# MiniRS485_RJ45-MySens-v1_7.net
KiCad netlist of a schematic drawn in EAGLE
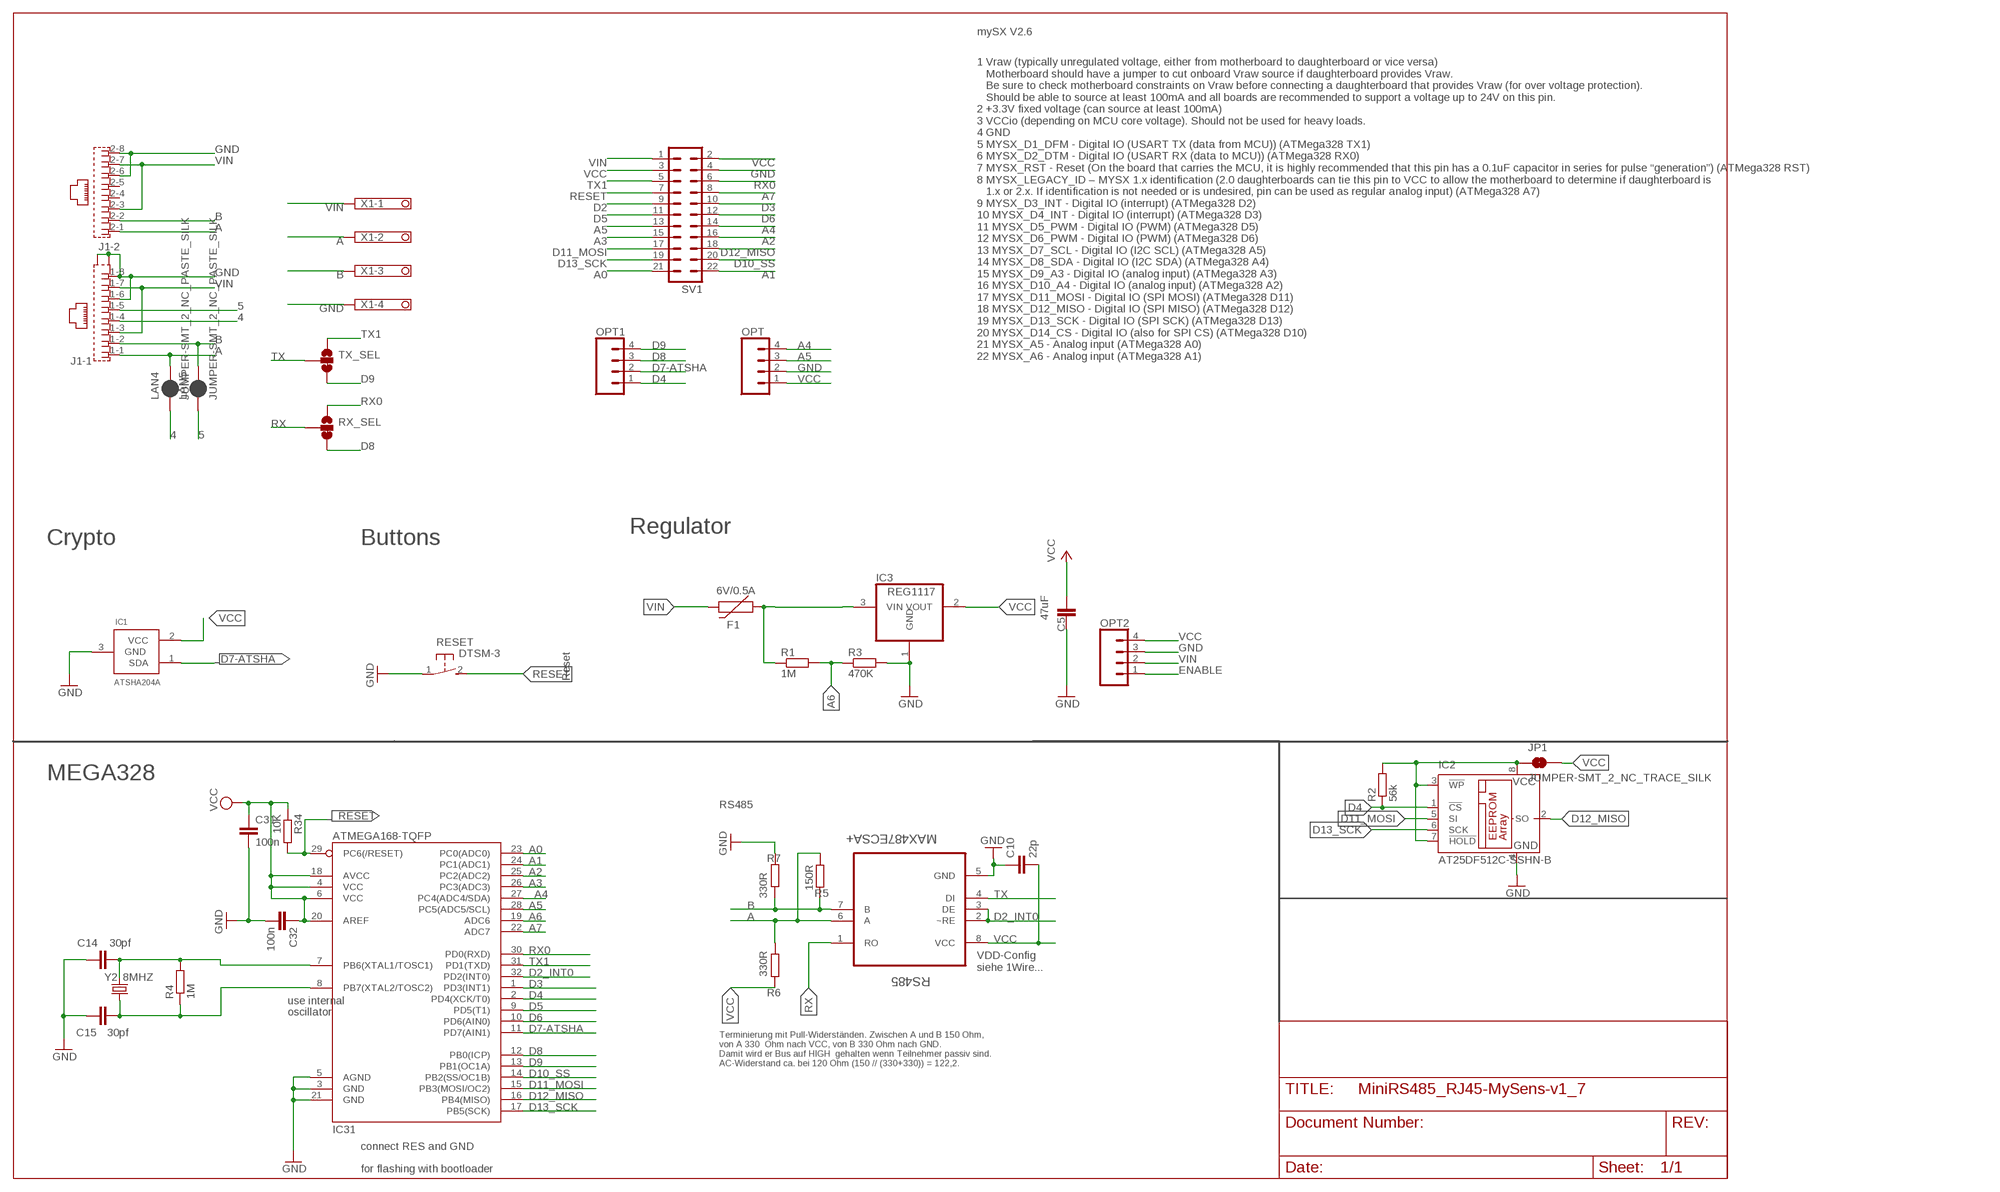
[diagram p0: schematic, sheet 1]

(export (version "E")
  (design (tool "Eeschema 10.0.6"))
  (components
    (comp (ref "C5")
      (value "47uF")
      (footprint "eagle-import:C1210")
      (libsource (lib "eagle-import") (part "C-EUC1210"))
    )
    (comp (ref "C10")
      (value "22p")
      (footprint "eagle-import:C0805")
      (libsource (lib "eagle-import") (part "C-EUC0805"))
    )
    (comp (ref "C14")
      (value "30pf")
      (footprint "eagle-import:C0805")
      (libsource (lib "eagle-import") (part "resistor_C-EUC0805"))
    )
    (comp (ref "C15")
      (value "30pf")
      (footprint "eagle-import:C0805")
      (libsource (lib "eagle-import") (part "resistor_C-EUC0805"))
    )
    (comp (ref "C31")
      (value "100n")
      (footprint "eagle-import:C0805")
      (libsource (lib "eagle-import") (part "C-EUC0805"))
    )
    (comp (ref "C32")
      (value "100n")
      (footprint "eagle-import:C0805")
      (libsource (lib "eagle-import") (part "C-EUC0805"))
    )
    (comp (ref "F1")
      (value "6V/0.5A")
      (footprint "eagle-import:1206")
      (libsource (lib "eagle-import") (part "PPTC_HALF-AMP"))
    )
    (comp (ref "IC1")
      (value "ATSHA204A")
      (footprint "eagle-import:SOT23")
      (libsource (lib "eagle-import") (part "ATSHA204A"))
    )
    (comp (ref "IC2")
      (value "AT25DF512C-SSHN-B")
      (footprint "eagle-import:SO-08")
      (fields (field (name "MF") "MICROCHIP") (field (name "MPN") "25AA080/SN"))
      (libsource (lib "eagle-import") (part "25SNAA080"))
    )
    (comp (ref "IC3")
      (value "REG1117")
      (footprint "eagle-import:SOT223")
      (libsource (lib "eagle-import") (part "REG1117"))
    )
    (comp (ref "IC31")
      (value "ATMEGA168-TQFP")
      (footprint "eagle-import:TQFP32-08")
      (libsource (lib "eagle-import") (part "ATMEGA168-TQFP"))
    )
    (comp (ref "J1")
      (value "RJ45_2X_NARROW_SHILDPINS_NOCASE")
      (footprint "eagle-import:RJ45_2X_NARROW_SHILDPINS_NOCASE")
      (libsource (lib "eagle-import") (part "RJ45_2X_NARROW_SHILDPINS_NOCASE"))
    )
    (comp (ref "JP1")
      (value "JUMPER-SMT_2_NC_TRACE_SILK")
      (footprint "eagle-import:SMT-JUMPER_2_NC_TRACE_SILK")
      (libsource (lib "eagle-import") (part "JUMPER-SMT_2_NC_TRACE_SILK"))
    )
    (comp (ref "LAN4")
      (value "JUMPER-SMT_2_NC_PASTE_SILK")
      (footprint "eagle-import:SMT-JUMPER_2_NC_PASTE_SILK")
      (libsource (lib "eagle-import") (part "JUMPER-SMT_2_NC_PASTE_SILK"))
    )
    (comp (ref "LAN5")
      (value "JUMPER-SMT_2_NC_PASTE_SILK")
      (footprint "eagle-import:SMT-JUMPER_2_NC_PASTE_SILK")
      (libsource (lib "eagle-import") (part "JUMPER-SMT_2_NC_PASTE_SILK"))
    )
    (comp (ref "OPT")
      (value "CONN_04")
      (footprint "eagle-import:1X04")
      (libsource (lib "eagle-import") (part "CONN_04"))
    )
    (comp (ref "OPT1")
      (value "CONN_04")
      (footprint "eagle-import:1X04")
      (libsource (lib "eagle-import") (part "CONN_04"))
    )
    (comp (ref "OPT2")
      (value "CONN_04")
      (footprint "eagle-import:1X04")
      (libsource (lib "eagle-import") (part "CONN_04"))
    )
    (comp (ref "R1")
      (value "1M")
      (footprint "eagle-import:M0805")
      (libsource (lib "eagle-import") (part "R-EU_M0805"))
    )
    (comp (ref "R2")
      (value "56k")
      (footprint "eagle-import:M0805")
      (libsource (lib "eagle-import") (part "resistor_R-EU_M0805"))
    )
    (comp (ref "R3")
      (value "470K")
      (footprint "eagle-import:R0805")
      (libsource (lib "eagle-import") (part "R-EU_R0805"))
    )
    (comp (ref "R4")
      (value "1M")
      (footprint "eagle-import:M0805")
      (libsource (lib "eagle-import") (part "R-EU_M0805"))
    )
    (comp (ref "R5")
      (value "150R")
      (footprint "eagle-import:R0805")
      (libsource (lib "eagle-import") (part "R-EU_R0805"))
    )
    (comp (ref "R6")
      (value "330R")
      (footprint "eagle-import:R0805")
      (libsource (lib "eagle-import") (part "R-EU_R0805"))
    )
    (comp (ref "R7")
      (value "330R")
      (footprint "eagle-import:R0805")
      (libsource (lib "eagle-import") (part "R-EU_R0805"))
    )
    (comp (ref "R34")
      (value "10K")
      (footprint "eagle-import:R0805")
      (libsource (lib "eagle-import") (part "R-EU_R0805"))
    )
    (comp (ref "RESET")
      (value "DTSM-3")
      (footprint "eagle-import:DTSM-3")
      (libsource (lib "eagle-import") (part "DTSM-3"))
    )
    (comp (ref "RS485")
      (value "MAX487ECSA+")
      (footprint "eagle-import:SOIC127P600X175-8N")
      (libsource (lib "eagle-import") (part "MAX487ECSA+"))
    )
    (comp (ref "RX_SEL")
      (value "JUMPER-SMT_3_1-NC_TRACE_SILK")
      (footprint "eagle-import:SMT-JUMPER_3_1-NC_TRACE_SILK")
      (libsource (lib "eagle-import") (part "JUMPER-SMT_3_1-NC_TRACE_SILK"))
    )
    (comp (ref "SV1")
      (value "MA11-2")
      (footprint "eagle-import:MA11-2")
      (libsource (lib "eagle-import") (part "MA11-2"))
    )
    (comp (ref "TX_SEL")
      (value "JUMPER-SMT_3_1-NC_TRACE_SILK")
      (footprint "eagle-import:SMT-JUMPER_3_1-NC_TRACE_SILK")
      (libsource (lib "eagle-import") (part "JUMPER-SMT_3_1-NC_TRACE_SILK"))
    )
    (comp (ref "X1")
      (value "1751264")
      (footprint "eagle-import:1751264")
      (libsource (lib "eagle-import") (part "1751264"))
    )
    (comp (ref "Y2")
      (value "8MHZ")
      (footprint "eagle-import:CRYSTAL-TXC-7A")
      (libsource (lib "eagle-import") (part "CRYSTALTXC-7A"))
    )
  )
  (nets
    (net (code "1") (name "/4") (class "Default")
      (node (ref "J1") (pin "1-4") (pinfunction "4_1-4") (pintype "passive"))
      (node (ref "LAN4") (pin "1") (pinfunction "1_1") (pintype "passive"))
    )
    (net (code "2") (name "/5") (class "Default")
      (node (ref "J1") (pin "1-5") (pinfunction "5_1-5") (pintype "passive"))
      (node (ref "LAN5") (pin "1") (pinfunction "1_1") (pintype "passive"))
    )
    (net (code "3") (name "/A") (class "Default")
      (node (ref "J1") (pin "1-1") (pinfunction "1_1-1") (pintype "passive"))
      (node (ref "J1") (pin "2-1") (pinfunction "1_2-1") (pintype "passive"))
      (node (ref "LAN4") (pin "2") (pinfunction "2_2") (pintype "passive"))
      (node (ref "R5") (pin "1") (pinfunction "1_1") (pintype "passive"))
      (node (ref "R6") (pin "2") (pinfunction "2_2") (pintype "passive"))
      (node (ref "RS485") (pin "6") (pinfunction "A_6") (pintype "bidirectional"))
      (node (ref "X1") (pin "2") (pinfunction "K_2") (pintype "passive"))
    )
    (net (code "4") (name "/A0") (class "Default")
      (node (ref "IC31") (pin "23") (pinfunction "PC0(ADC0)_23") (pintype "bidirectional"))
      (node (ref "SV1") (pin "21") (pinfunction "21_21") (pintype "passive"))
    )
    (net (code "5") (name "/A1") (class "Default")
      (node (ref "IC31") (pin "24") (pinfunction "PC1(ADC1)_24") (pintype "bidirectional"))
      (node (ref "SV1") (pin "22") (pinfunction "22_22") (pintype "passive"))
    )
    (net (code "6") (name "/A2") (class "Default")
      (node (ref "IC31") (pin "25") (pinfunction "PC2(ADC2)_25") (pintype "bidirectional"))
      (node (ref "SV1") (pin "16") (pinfunction "16_16") (pintype "passive"))
    )
    (net (code "7") (name "/A3") (class "Default")
      (node (ref "IC31") (pin "26") (pinfunction "PC3(ADC3)_26") (pintype "bidirectional"))
      (node (ref "SV1") (pin "15") (pinfunction "15_15") (pintype "passive"))
    )
    (net (code "8") (name "/A4") (class "Default")
      (node (ref "IC31") (pin "27") (pinfunction "PC4(ADC4/SDA)_27") (pintype "bidirectional"))
      (node (ref "OPT") (pin "4") (pinfunction "4_4") (pintype "passive"))
      (node (ref "SV1") (pin "14") (pinfunction "14_14") (pintype "passive"))
    )
    (net (code "9") (name "/A5") (class "Default")
      (node (ref "IC31") (pin "28") (pinfunction "PC5(ADC5/SCL)_28") (pintype "bidirectional"))
      (node (ref "OPT") (pin "3") (pinfunction "3_3") (pintype "passive"))
      (node (ref "SV1") (pin "13") (pinfunction "13_13") (pintype "passive"))
    )
    (net (code "10") (name "/A7") (class "Default")
      (node (ref "IC31") (pin "22") (pinfunction "ADC7_22") (pintype "bidirectional"))
      (node (ref "SV1") (pin "8") (pinfunction "8_8") (pintype "passive"))
    )
    (net (code "11") (name "/B") (class "Default")
      (node (ref "J1") (pin "1-2") (pinfunction "2_1-2") (pintype "passive"))
      (node (ref "J1") (pin "2-2") (pinfunction "2_2-2") (pintype "passive"))
      (node (ref "LAN5") (pin "2") (pinfunction "2_2") (pintype "passive"))
      (node (ref "R5") (pin "2") (pinfunction "2_2") (pintype "passive"))
      (node (ref "R7") (pin "1") (pinfunction "1_1") (pintype "passive"))
      (node (ref "RS485") (pin "7") (pinfunction "B_7") (pintype "bidirectional"))
      (node (ref "X1") (pin "3") (pinfunction "K_3") (pintype "passive"))
    )
    (net (code "12") (name "/D2") (class "Default")
      (node (ref "SV1") (pin "9") (pinfunction "9_9") (pintype "passive"))
    )
    (net (code "13") (name "/D2_INT0") (class "Default")
      (node (ref "IC31") (pin "32") (pinfunction "PD2(INT0)_32") (pintype "bidirectional"))
      (node (ref "RS485") (pin "2") (pinfunction "~{RE}_2") (pintype "input"))
      (node (ref "RS485") (pin "3") (pinfunction "DE_3") (pintype "input"))
    )
    (net (code "14") (name "/D3") (class "Default")
      (node (ref "IC31") (pin "1") (pinfunction "PD3(INT1)_1") (pintype "bidirectional"))
      (node (ref "SV1") (pin "10") (pinfunction "10_10") (pintype "passive"))
    )
    (net (code "15") (name "/D5") (class "Default")
      (node (ref "IC31") (pin "9") (pinfunction "PD5(T1)_9") (pintype "bidirectional"))
      (node (ref "SV1") (pin "11") (pinfunction "11_11") (pintype "passive"))
    )
    (net (code "16") (name "/D6") (class "Default")
      (node (ref "IC31") (pin "10") (pinfunction "PD6(AIN0)_10") (pintype "bidirectional"))
      (node (ref "SV1") (pin "12") (pinfunction "12_12") (pintype "passive"))
    )
    (net (code "17") (name "/D7-ATSHA") (class "Default")
      (node (ref "IC1") (pin "1") (pinfunction "SDA_1") (pintype "bidirectional"))
      (node (ref "IC31") (pin "11") (pinfunction "PD7(AIN1)_11") (pintype "bidirectional"))
      (node (ref "OPT1") (pin "2") (pinfunction "2_2") (pintype "passive"))
    )
    (net (code "18") (name "/D8") (class "Default")
      (node (ref "IC31") (pin "12") (pinfunction "PB0(ICP)_12") (pintype "bidirectional"))
      (node (ref "OPT1") (pin "3") (pinfunction "3_3") (pintype "passive"))
      (node (ref "RX_SEL") (pin "3") (pinfunction "3_3") (pintype "passive"))
    )
    (net (code "19") (name "/D9") (class "Default")
      (node (ref "IC31") (pin "13") (pinfunction "PB1(OC1A)_13") (pintype "bidirectional"))
      (node (ref "OPT1") (pin "4") (pinfunction "4_4") (pintype "passive"))
      (node (ref "TX_SEL") (pin "3") (pinfunction "3_3") (pintype "passive"))
    )
    (net (code "20") (name "/D10_SS") (class "Default")
      (node (ref "IC31") (pin "14") (pinfunction "PB2(SS/OC1B)_14") (pintype "bidirectional"))
      (node (ref "SV1") (pin "20") (pinfunction "20_20") (pintype "passive"))
    )
    (net (code "21") (name "/ENABLE") (class "Default")
      (node (ref "OPT2") (pin "1") (pinfunction "1_1") (pintype "passive"))
    )
    (net (code "22") (name "/RX0") (class "Default")
      (node (ref "IC31") (pin "30") (pinfunction "PD0(RXD)_30") (pintype "bidirectional"))
      (node (ref "RX_SEL") (pin "1") (pinfunction "1_1") (pintype "passive"))
      (node (ref "SV1") (pin "6") (pinfunction "6_6") (pintype "passive"))
    )
    (net (code "23") (name "/TX") (class "Default")
      (node (ref "RS485") (pin "4") (pinfunction "DI_4") (pintype "input"))
      (node (ref "TX_SEL") (pin "2") (pinfunction "2_2") (pintype "passive"))
    )
    (net (code "24") (name "/TX1") (class "Default")
      (node (ref "IC31") (pin "31") (pinfunction "PD1(TXD)_31") (pintype "bidirectional"))
      (node (ref "SV1") (pin "5") (pinfunction "5_5") (pintype "passive"))
      (node (ref "TX_SEL") (pin "1") (pinfunction "1_1") (pintype "passive"))
    )
    (net (code "25") (name "A6") (class "Default")
      (node (ref "IC31") (pin "19") (pinfunction "ADC6_19") (pintype "bidirectional"))
      (node (ref "R1") (pin "2") (pinfunction "2_2") (pintype "passive"))
      (node (ref "R3") (pin "1") (pinfunction "1_1") (pintype "passive"))
    )
    (net (code "26") (name "D4") (class "Default")
      (node (ref "IC2") (pin "1") (pinfunction "~{CS}_1") (pintype "input"))
      (node (ref "IC31") (pin "2") (pinfunction "PD4(XCK/T0)_2") (pintype "bidirectional"))
      (node (ref "OPT1") (pin "1") (pinfunction "1_1") (pintype "passive"))
      (node (ref "R2") (pin "1") (pinfunction "1_1") (pintype "passive"))
    )
    (net (code "27") (name "D11_MOSI") (class "Default")
      (node (ref "IC2") (pin "5") (pinfunction "SI_5") (pintype "input"))
      (node (ref "IC31") (pin "15") (pinfunction "PB3(MOSI/OC2)_15") (pintype "bidirectional"))
      (node (ref "SV1") (pin "17") (pinfunction "17_17") (pintype "passive"))
    )
    (net (code "28") (name "D12_MISO") (class "Default")
      (node (ref "IC2") (pin "2") (pinfunction "SO_2") (pintype "bidirectional"))
      (node (ref "IC31") (pin "16") (pinfunction "PB4(MISO)_16") (pintype "bidirectional"))
      (node (ref "SV1") (pin "18") (pinfunction "18_18") (pintype "passive"))
    )
    (net (code "29") (name "D13_SCK") (class "Default")
      (node (ref "IC2") (pin "6") (pinfunction "SCK_6") (pintype "input"))
      (node (ref "IC31") (pin "17") (pinfunction "PB5(SCK)_17") (pintype "bidirectional"))
      (node (ref "SV1") (pin "19") (pinfunction "19_19") (pintype "passive"))
    )
    (net (code "30") (name "GND") (class "Default")
      (node (ref "C10") (pin "1") (pinfunction "1_1") (pintype "passive"))
      (node (ref "C14") (pin "1") (pinfunction "1_1") (pintype "passive"))
      (node (ref "C15") (pin "1") (pinfunction "1_1") (pintype "passive"))
      (node (ref "C31") (pin "2") (pinfunction "2_2") (pintype "passive"))
      (node (ref "C32") (pin "2") (pinfunction "2_2") (pintype "passive"))
      (node (ref "C5") (pin "1") (pinfunction "1_1") (pintype "passive"))
      (node (ref "IC1") (pin "3") (pinfunction "GND_3") (pintype "bidirectional"))
      (node (ref "IC2") (pin "4") (pinfunction "GND_4") (pintype "power_in"))
      (node (ref "IC3") (pin "1") (pinfunction "GND_1") (pintype "power_in"))
      (node (ref "IC31") (pin "21") (pinfunction "GND_21") (pintype "bidirectional"))
      (node (ref "IC31") (pin "3") (pinfunction "GND_3") (pintype "bidirectional"))
      (node (ref "IC31") (pin "5") (pinfunction "AGND_5") (pintype "bidirectional"))
      (node (ref "J1") (pin "1-6") (pinfunction "6_1-6") (pintype "passive"))
      (node (ref "J1") (pin "1-8") (pinfunction "8_1-8") (pintype "passive"))
      (node (ref "J1") (pin "2-6") (pinfunction "6_2-6") (pintype "passive"))
      (node (ref "J1") (pin "2-8") (pinfunction "8_2-8") (pintype "passive"))
      (node (ref "J1") (pin "G1") (pinfunction "S1_G1") (pintype "passive"))
      (node (ref "J1") (pin "G3") (pinfunction "S2_G3") (pintype "passive"))
      (node (ref "OPT") (pin "2") (pinfunction "2_2") (pintype "passive"))
      (node (ref "OPT2") (pin "3") (pinfunction "3_3") (pintype "passive"))
      (node (ref "R3") (pin "2") (pinfunction "2_2") (pintype "passive"))
      (node (ref "R7") (pin "2") (pinfunction "2_2") (pintype "passive"))
      (node (ref "RESET") (pin "1") (pinfunction "1_1") (pintype "passive"))
      (node (ref "RS485") (pin "5") (pinfunction "GND_5") (pintype "passive"))
      (node (ref "SV1") (pin "4") (pinfunction "4_4") (pintype "passive"))
      (node (ref "X1") (pin "4") (pinfunction "K_4") (pintype "passive"))
    )
    (net (code "31") (name "Net-(IC2-VCC)") (class "Default")
      (node (ref "IC2") (pin "3") (pinfunction "~{WP}_3") (pintype "input"))
      (node (ref "IC2") (pin "7") (pinfunction "~{HOLD}_7") (pintype "input"))
      (node (ref "IC2") (pin "8") (pinfunction "VCC_8") (pintype "power_in"))
      (node (ref "JP1") (pin "1") (pinfunction "1_1") (pintype "passive"))
      (node (ref "R2") (pin "2") (pinfunction "2_2") (pintype "passive"))
    )
    (net (code "32") (name "Net-(IC3-VIN)") (class "Default")
      (node (ref "F1") (pin "1") (pinfunction "1_1") (pintype "bidirectional"))
      (node (ref "IC3") (pin "3") (pinfunction "VIN_3") (pintype "input"))
      (node (ref "R1") (pin "1") (pinfunction "1_1") (pintype "passive"))
    )
    (net (code "33") (name "Net-(IC31-PB6(XTAL1{slash}TOSC1))") (class "Default")
      (node (ref "C14") (pin "2") (pinfunction "2_2") (pintype "passive"))
      (node (ref "IC31") (pin "7") (pinfunction "PB6(XTAL1/TOSC1)_7") (pintype "bidirectional"))
      (node (ref "R4") (pin "2") (pinfunction "2_2") (pintype "passive"))
      (node (ref "Y2") (pin "P$2") (pinfunction "2_P$2") (pintype "passive"))
    )
    (net (code "34") (name "Net-(IC31-PB7(XTAL2{slash}TOSC2))") (class "Default")
      (node (ref "C15") (pin "2") (pinfunction "2_2") (pintype "passive"))
      (node (ref "IC31") (pin "8") (pinfunction "PB7(XTAL2/TOSC2)_8") (pintype "bidirectional"))
      (node (ref "R4") (pin "1") (pinfunction "1_1") (pintype "passive"))
      (node (ref "Y2") (pin "P$1") (pinfunction "1_P$1") (pintype "passive"))
    )
    (net (code "35") (name "RESET") (class "Default")
      (node (ref "IC31") (pin "29") (pinfunction "PC6(/RESET)_29") (pintype "bidirectional"))
      (node (ref "R34") (pin "2") (pinfunction "2_2") (pintype "passive"))
      (node (ref "RESET") (pin "2") (pinfunction "2_2") (pintype "passive"))
      (node (ref "SV1") (pin "7") (pinfunction "7_7") (pintype "passive"))
    )
    (net (code "36") (name "RX") (class "Default")
      (node (ref "RS485") (pin "1") (pinfunction "RO_1") (pintype "output"))
      (node (ref "RX_SEL") (pin "2") (pinfunction "2_2") (pintype "passive"))
    )
    (net (code "37") (name "VCC") (class "Default")
      (node (ref "C10") (pin "2") (pinfunction "2_2") (pintype "passive"))
      (node (ref "C31") (pin "1") (pinfunction "1_1") (pintype "passive"))
      (node (ref "C32") (pin "1") (pinfunction "1_1") (pintype "passive"))
      (node (ref "C5") (pin "2") (pinfunction "2_2") (pintype "passive"))
      (node (ref "IC1") (pin "2") (pinfunction "VCC_2") (pintype "bidirectional"))
      (node (ref "IC3") (pin "2") (pinfunction "VOUT_2") (pintype "output"))
      (node (ref "IC31") (pin "18") (pinfunction "AVCC_18") (pintype "bidirectional"))
      (node (ref "IC31") (pin "20") (pinfunction "AREF_20") (pintype "bidirectional"))
      (node (ref "IC31") (pin "4") (pinfunction "VCC_4") (pintype "bidirectional"))
      (node (ref "IC31") (pin "6") (pinfunction "VCC_6") (pintype "bidirectional"))
      (node (ref "JP1") (pin "2") (pinfunction "2_2") (pintype "passive"))
      (node (ref "OPT") (pin "1") (pinfunction "1_1") (pintype "passive"))
      (node (ref "OPT2") (pin "4") (pinfunction "4_4") (pintype "passive"))
      (node (ref "R34") (pin "1") (pinfunction "1_1") (pintype "passive"))
      (node (ref "R6") (pin "1") (pinfunction "1_1") (pintype "passive"))
      (node (ref "RS485") (pin "8") (pinfunction "VCC_8") (pintype "power_in"))
      (node (ref "SV1") (pin "2") (pinfunction "2_2") (pintype "passive"))
      (node (ref "SV1") (pin "3") (pinfunction "3_3") (pintype "passive"))
    )
    (net (code "38") (name "VIN") (class "Default")
      (node (ref "F1") (pin "2") (pinfunction "2_2") (pintype "bidirectional"))
      (node (ref "J1") (pin "1-3") (pinfunction "3_1-3") (pintype "passive"))
      (node (ref "J1") (pin "1-7") (pinfunction "7_1-7") (pintype "passive"))
      (node (ref "J1") (pin "2-3") (pinfunction "3_2-3") (pintype "passive"))
      (node (ref "J1") (pin "2-7") (pinfunction "7_2-7") (pintype "passive"))
      (node (ref "OPT2") (pin "2") (pinfunction "2_2") (pintype "passive"))
      (node (ref "SV1") (pin "1") (pinfunction "1_1") (pintype "passive"))
      (node (ref "X1") (pin "1") (pinfunction "K_1") (pintype "passive"))
    )
    (net (code "39") (name "unconnected-(J1B-4-Pad2-4)") (class "Default")
      (node (ref "J1") (pin "2-4") (pinfunction "4_2-4") (pintype "passive"))
    )
    (net (code "40") (name "unconnected-(J1B-5-Pad2-5)") (class "Default")
      (node (ref "J1") (pin "2-5") (pinfunction "5_2-5") (pintype "passive"))
    )
  )
)
